# I2S.net
KiCad netlist of a schematic drawn in Altium Designer
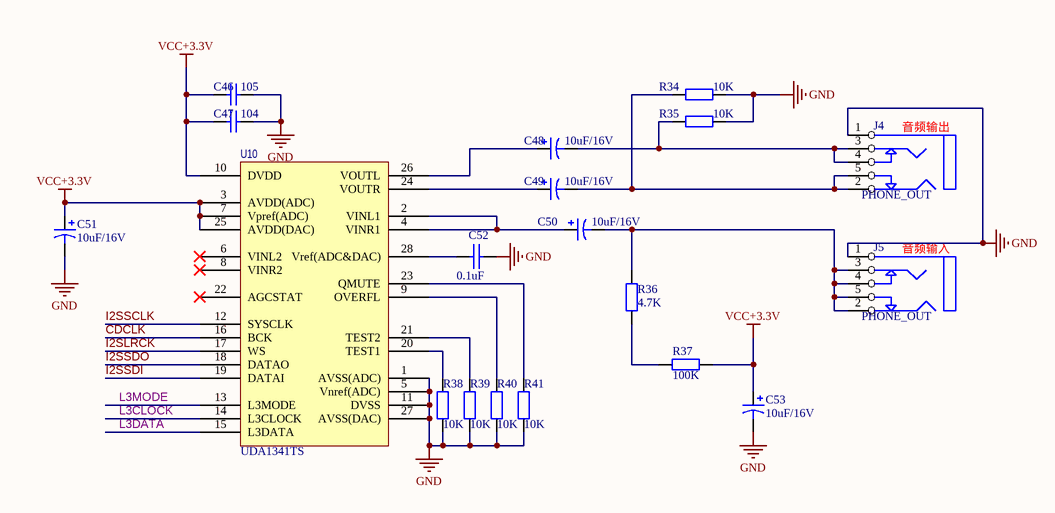
[diagram p0: I2S.SchDoc]

(export (version "E")
  (design (tool "Eeschema 10.0.6"))
  (components
    (comp (ref "C46")
      (value "105")
      (footprint "0805")
      (description "Capacitor")
      (fields (field (name "Comment") "Cap") (field (name "PUBLISHER") "Altium Limited"))
      (libsource (lib "自制Miscellaneous Devices库") (part "Cap"))
    )
    (comp (ref "C47")
      (value "104")
      (footprint "0805")
      (description "Capacitor")
      (fields (field (name "Comment") "Cap") (field (name "PUBLISHER") "Altium Limited"))
      (libsource (lib "自制Miscellaneous Devices库") (part "Cap"))
    )
    (comp (ref "C48")
      (value "10uF/16V")
      (footprint "1206[3216]")
      (description "Polarized Capacitor (Axial)")
      (fields (field (name "Comment") "Cap Pol2") (field (name "PUBLISHER") "Altium Limited"))
      (libsource (lib "自制Miscellaneous Devices库") (part "Cap Pol2"))
    )
    (comp (ref "C49")
      (value "10uF/16V")
      (footprint "1206[3216]")
      (description "Polarized Capacitor (Axial)")
      (fields (field (name "Comment") "Cap Pol2") (field (name "PUBLISHER") "Altium Limited"))
      (libsource (lib "自制Miscellaneous Devices库") (part "Cap Pol2"))
    )
    (comp (ref "C50")
      (value "10uF/16V")
      (footprint "1206[3216]")
      (description "Polarized Capacitor (Axial)")
      (fields (field (name "Comment") "Cap Pol2") (field (name "PUBLISHER") "Altium Limited"))
      (libsource (lib "自制Miscellaneous Devices库") (part "Cap Pol2"))
    )
    (comp (ref "C51")
      (value "10uF/16V")
      (footprint "1206[3216]")
      (description "Polarized Capacitor (Axial)")
      (fields (field (name "Comment") "Cap Pol2") (field (name "PUBLISHER") "Altium Limited"))
      (libsource (lib "自制Miscellaneous Devices库") (part "Cap Pol2"))
    )
    (comp (ref "C52")
      (value "0.1uF")
      (footprint "0805")
      (description "Capacitor")
      (libsource (lib "*") (part "CAP"))
    )
    (comp (ref "C53")
      (value "10uF/16V")
      (footprint "1206[3216]")
      (description "Polarized Capacitor (Axial)")
      (fields (field (name "Comment") "Cap Pol2") (field (name "PUBLISHER") "Altium Limited"))
      (libsource (lib "自制Miscellaneous Devices库") (part "Cap Pol2"))
    )
    (comp (ref "J4")
      (value "PHONE_OUT")
      (footprint "PJ-215-B")
      (libsource (lib "自制原理图元件库") (part "PHONEJACK STEREO SW"))
    )
    (comp (ref "J5")
      (value "PHONE_OUT")
      (footprint "PJ-215-B")
      (libsource (lib "自制原理图元件库") (part "PHONEJACK STEREO SW"))
    )
    (comp (ref "R34")
      (value "10K")
      (footprint "0805")
      (description "Resistor")
      (fields (field (name "Comment") "Res2") (field (name "PUBLISHER") "Altium Limited"))
      (libsource (lib "") (part "Res2_1"))
    )
    (comp (ref "R35")
      (value "10K")
      (footprint "0805")
      (description "Resistor")
      (fields (field (name "Comment") "Res2") (field (name "PUBLISHER") "Altium Limited"))
      (libsource (lib "") (part "Res2_1"))
    )
    (comp (ref "R36")
      (value "4.7K")
      (footprint "0805")
      (description "Resistor")
      (fields (field (name "Comment") "Res2") (field (name "PUBLISHER") "Altium Limited"))
      (libsource (lib "自制Miscellaneous Devices库") (part "Res2"))
    )
    (comp (ref "R37")
      (value "100K")
      (footprint "0805")
      (description "Resistor")
      (fields (field (name "Comment") "Res2") (field (name "PUBLISHER") "Altium Limited"))
      (libsource (lib "") (part "Res2_2"))
    )
    (comp (ref "R38")
      (value "10K")
      (footprint "0805")
      (description "Resistor")
      (fields (field (name "Comment") "Res2") (field (name "PUBLISHER") "Altium Limited"))
      (libsource (lib "自制Miscellaneous Devices库") (part "Res2"))
    )
    (comp (ref "R39")
      (value "10K")
      (footprint "0805")
      (description "Resistor")
      (fields (field (name "Comment") "Res2") (field (name "PUBLISHER") "Altium Limited"))
      (libsource (lib "自制Miscellaneous Devices库") (part "Res2"))
    )
    (comp (ref "R40")
      (value "10K")
      (footprint "0805")
      (description "Resistor")
      (fields (field (name "Comment") "Res2") (field (name "PUBLISHER") "Altium Limited"))
      (libsource (lib "自制Miscellaneous Devices库") (part "Res2"))
    )
    (comp (ref "R41")
      (value "10K")
      (footprint "0805")
      (description "Resistor")
      (fields (field (name "Comment") "Res2") (field (name "PUBLISHER") "Altium Limited"))
      (libsource (lib "自制Miscellaneous Devices库") (part "Res2"))
    )
    (comp (ref "U10")
      (value "UDA1341TS")
      (footprint "SOP_UDA1341TS_1")
      (libsource (lib "自制原理图元件库") (part "UDA1341TS_1"))
    )
  )
  (nets
    (net (code "1") (name "/CDCLK") (class "Default")
      (node (ref "U10") (pin "16") (pinfunction "BCK_16") (pintype "passive"))
    )
    (net (code "2") (name "/I2SLRCK") (class "Default")
      (node (ref "U10") (pin "17") (pinfunction "WS_17") (pintype "passive"))
    )
    (net (code "3") (name "/I2SSCLK") (class "Default")
      (node (ref "U10") (pin "12") (pinfunction "SYSCLK_12") (pintype "passive"))
    )
    (net (code "4") (name "/I2SSDI") (class "Default")
      (node (ref "U10") (pin "19") (pinfunction "DATAI_19") (pintype "passive"))
    )
    (net (code "5") (name "/I2SSDO") (class "Default")
      (node (ref "U10") (pin "18") (pinfunction "DATAO_18") (pintype "passive"))
    )
    (net (code "6") (name "/L3CLOCK") (class "Default")
      (node (ref "U10") (pin "14") (pinfunction "L3CLOCK_14") (pintype "passive"))
    )
    (net (code "7") (name "/L3DATA") (class "Default")
      (node (ref "U10") (pin "15") (pinfunction "L3DATA_15") (pintype "passive"))
    )
    (net (code "8") (name "/L3MODE") (class "Default")
      (node (ref "U10") (pin "13") (pinfunction "L3MODE_13") (pintype "passive"))
    )
    (net (code "9") (name "GND") (class "Default")
      (node (ref "C46") (pin "1") (pinfunction "1_1") (pintype "passive"))
      (node (ref "C47") (pin "1") (pinfunction "1_1") (pintype "passive"))
      (node (ref "C51") (pin "2") (pinfunction "2_2") (pintype "passive"))
      (node (ref "C52") (pin "2") (pinfunction "2_2") (pintype "passive"))
      (node (ref "C53") (pin "2") (pinfunction "2_2") (pintype "passive"))
      (node (ref "J4") (pin "1") (pinfunction "A_1") (pintype "passive"))
      (node (ref "J5") (pin "1") (pinfunction "A_1") (pintype "passive"))
      (node (ref "R34") (pin "2") (pinfunction "2_2") (pintype "passive"))
      (node (ref "R35") (pin "2") (pinfunction "2_2") (pintype "passive"))
      (node (ref "R38") (pin "1") (pinfunction "1_1") (pintype "passive"))
      (node (ref "R39") (pin "1") (pinfunction "1_1") (pintype "passive"))
      (node (ref "R40") (pin "1") (pinfunction "1_1") (pintype "passive"))
      (node (ref "R41") (pin "1") (pinfunction "1_1") (pintype "passive"))
      (node (ref "U10") (pin "1") (pinfunction "AVSS(ADC)_1") (pintype "passive"))
      (node (ref "U10") (pin "11") (pinfunction "DVSS_11") (pintype "passive"))
      (node (ref "U10") (pin "27") (pinfunction "AVSS(DAC)_27") (pintype "passive"))
      (node (ref "U10") (pin "5") (pinfunction "Vnref(ADC)_5") (pintype "passive"))
    )
    (net (code "10") (name "Net-(J4-B)") (class "Default")
      (node (ref "C49") (pin "2") (pinfunction "2_2") (pintype "passive"))
      (node (ref "J4") (pin "2") (pinfunction "B_2") (pintype "passive"))
      (node (ref "J4") (pin "5") (pinfunction "F_5") (pintype "passive"))
      (node (ref "R34") (pin "1") (pinfunction "1_1") (pintype "passive"))
    )
    (net (code "11") (name "Net-(J4-C)") (class "Default")
      (node (ref "C48") (pin "2") (pinfunction "2_2") (pintype "passive"))
      (node (ref "J4") (pin "3") (pinfunction "C_3") (pintype "passive"))
      (node (ref "J4") (pin "4") (pinfunction "E_4") (pintype "passive"))
      (node (ref "R35") (pin "1") (pinfunction "1_1") (pintype "passive"))
    )
    (net (code "12") (name "Net-(J5-B)") (class "Default")
      (node (ref "C50") (pin "2") (pinfunction "2_2") (pintype "passive"))
      (node (ref "J5") (pin "2") (pinfunction "B_2") (pintype "passive"))
      (node (ref "J5") (pin "3") (pinfunction "C_3") (pintype "passive"))
      (node (ref "J5") (pin "4") (pinfunction "E_4") (pintype "passive"))
      (node (ref "J5") (pin "5") (pinfunction "F_5") (pintype "passive"))
      (node (ref "R36") (pin "2") (pinfunction "2_2") (pintype "passive"))
    )
    (net (code "13") (name "Net-(R36-Pad1)") (class "Default")
      (node (ref "R36") (pin "1") (pinfunction "1_1") (pintype "passive"))
      (node (ref "R37") (pin "2") (pinfunction "2_2") (pintype "passive"))
    )
    (net (code "14") (name "Net-(U10-OVERFL)") (class "Default")
      (node (ref "R40") (pin "2") (pinfunction "2_2") (pintype "passive"))
      (node (ref "U10") (pin "9") (pinfunction "OVERFL_9") (pintype "passive"))
    )
    (net (code "15") (name "Net-(U10-QMUTE)") (class "Default")
      (node (ref "R41") (pin "2") (pinfunction "2_2") (pintype "passive"))
      (node (ref "U10") (pin "23") (pinfunction "QMUTE_23") (pintype "passive"))
    )
    (net (code "16") (name "Net-(U10-TEST1)") (class "Default")
      (node (ref "R38") (pin "2") (pinfunction "2_2") (pintype "passive"))
      (node (ref "U10") (pin "20") (pinfunction "TEST1_20") (pintype "passive"))
    )
    (net (code "17") (name "Net-(U10-TEST2)") (class "Default")
      (node (ref "R39") (pin "2") (pinfunction "2_2") (pintype "passive"))
      (node (ref "U10") (pin "21") (pinfunction "TEST2_21") (pintype "passive"))
    )
    (net (code "18") (name "Net-(U10-VINL1)") (class "Default")
      (node (ref "C50") (pin "1") (pinfunction "1_1") (pintype "passive"))
      (node (ref "U10") (pin "2") (pinfunction "VINL1_2") (pintype "passive"))
      (node (ref "U10") (pin "4") (pinfunction "VINR1_4") (pintype "passive"))
    )
    (net (code "19") (name "Net-(U10-VOUTL)") (class "Default")
      (node (ref "C48") (pin "1") (pinfunction "1_1") (pintype "passive"))
      (node (ref "U10") (pin "26") (pinfunction "VOUTL_26") (pintype "passive"))
    )
    (net (code "20") (name "Net-(U10-VOUTR)") (class "Default")
      (node (ref "C49") (pin "1") (pinfunction "1_1") (pintype "passive"))
      (node (ref "U10") (pin "24") (pinfunction "VOUTR_24") (pintype "passive"))
    )
    (net (code "21") (name "Net-(U10-Vref(ADC&DAC))") (class "Default")
      (node (ref "C52") (pin "1") (pinfunction "1_1") (pintype "passive"))
      (node (ref "U10") (pin "28") (pinfunction "Vref(ADC&DAC)_28") (pintype "passive"))
    )
    (net (code "22") (name "VCC+3.3V") (class "Default")
      (node (ref "C46") (pin "2") (pinfunction "2_2") (pintype "passive"))
      (node (ref "C47") (pin "2") (pinfunction "2_2") (pintype "passive"))
      (node (ref "C51") (pin "1") (pinfunction "1_1") (pintype "passive"))
      (node (ref "C53") (pin "1") (pinfunction "1_1") (pintype "passive"))
      (node (ref "R37") (pin "1") (pinfunction "1_1") (pintype "passive"))
      (node (ref "U10") (pin "10") (pinfunction "DVDD_10") (pintype "passive"))
      (node (ref "U10") (pin "25") (pinfunction "AVDD(DAC)_25") (pintype "passive"))
      (node (ref "U10") (pin "3") (pinfunction "AVDD(ADC)_3") (pintype "passive"))
      (node (ref "U10") (pin "7") (pinfunction "Vpref(ADC)_7") (pintype "passive"))
    )
    (net (code "23") (name "unconnected-(U10-AGCSTAT-Pad22)") (class "Default")
      (node (ref "U10") (pin "22") (pinfunction "AGCSTAT_22") (pintype "passive+no_connect"))
    )
    (net (code "24") (name "unconnected-(U10-VINL2-Pad6)") (class "Default")
      (node (ref "U10") (pin "6") (pinfunction "VINL2_6") (pintype "passive+no_connect"))
    )
    (net (code "25") (name "unconnected-(U10-VINR2-Pad8)") (class "Default")
      (node (ref "U10") (pin "8") (pinfunction "VINR2_8") (pintype "passive+no_connect"))
    )
  )
)
